# etapa1.net
KiCad netlist of a schematic drawn in Altium Designer
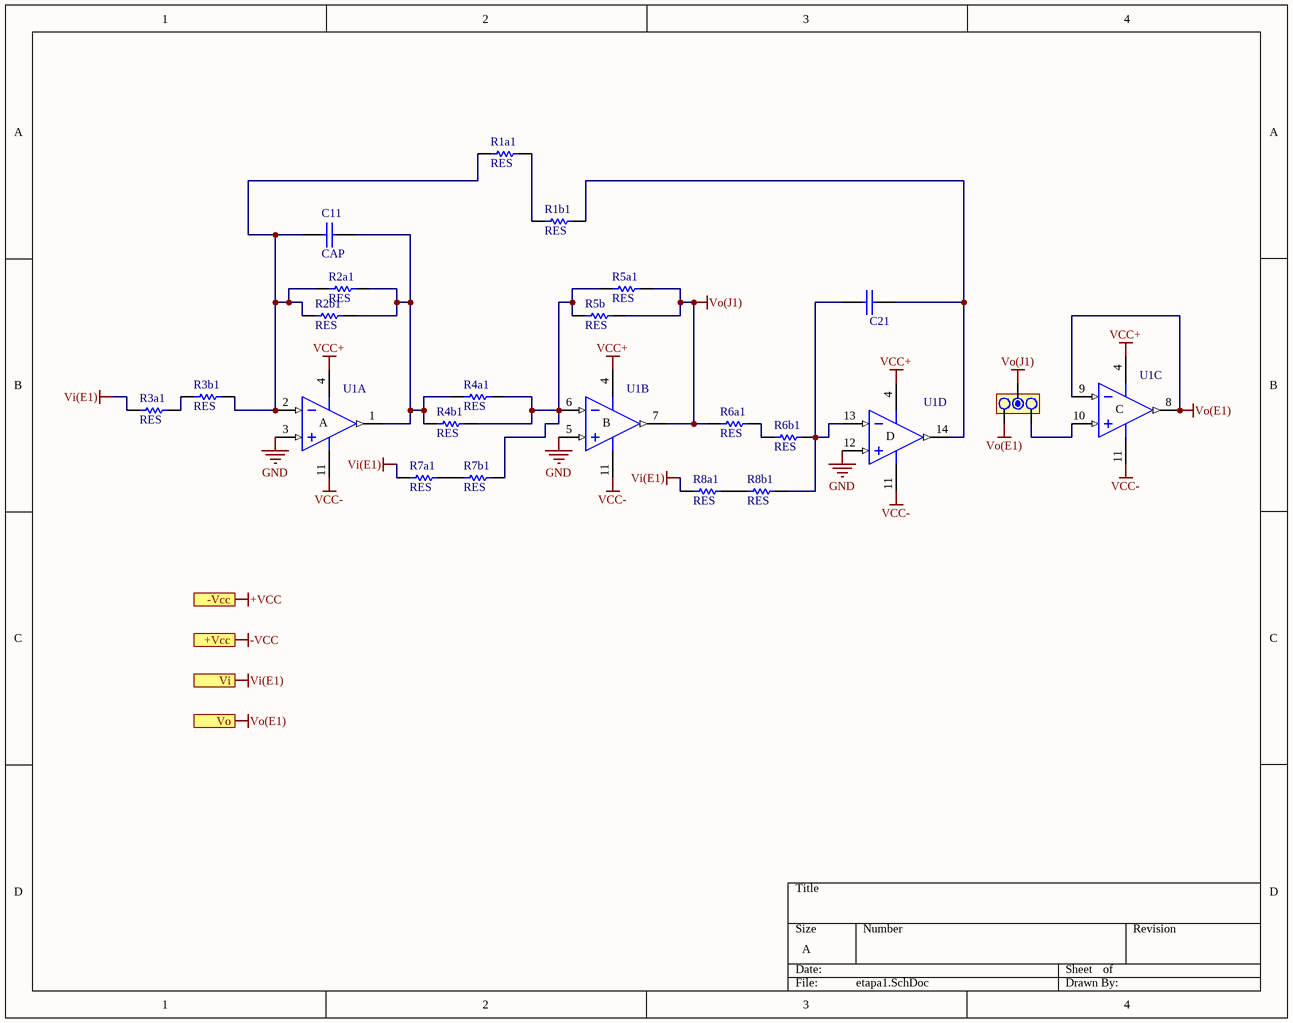
[diagram p0: etapa1.SchDoc]

(export (version "E")
  (design (tool "Eeschema 10.0.6"))
  (components
    (comp (ref "C11") (value "CAP") (footprint "CAP200") (libsource (lib "LIBEBAL") (part "CAP")))
    (comp (ref "C21") (value "CAP") (footprint "CAP200") (libsource (lib "LIBEBAL") (part "CAP")))
    (comp (ref "Jumper1") (value "JUMPER") (footprint "JUMPER3") (libsource (lib "LIBEBAL") (part "JUMPER3")))
    (comp (ref "R1a1") (value "RES") (footprint "0805") (libsource (lib "LIBEBAL") (part "RES")))
    (comp (ref "R1b1") (value "RES") (footprint "0805") (libsource (lib "LIBEBAL") (part "RES")))
    (comp (ref "R2a1") (value "RES") (footprint "0805") (libsource (lib "LIBEBAL") (part "RES")))
    (comp (ref "R2b1") (value "RES") (footprint "0805") (libsource (lib "LIBEBAL") (part "RES")))
    (comp (ref "R3a1") (value "RES") (footprint "0805") (libsource (lib "LIBEBAL") (part "RES")))
    (comp (ref "R3b1") (value "RES") (footprint "0805") (libsource (lib "LIBEBAL") (part "RES")))
    (comp (ref "R4a1") (value "RES") (footprint "0805") (libsource (lib "LIBEBAL") (part "RES")))
    (comp (ref "R4b1") (value "RES") (footprint "0805") (libsource (lib "LIBEBAL") (part "RES")))
    (comp (ref "R5a1") (value "RES") (footprint "0805") (libsource (lib "LIBEBAL") (part "RES")))
    (comp (ref "R5b") (value "RES") (footprint "0805") (libsource (lib "LIBEBAL") (part "RES")))
    (comp (ref "R6a1") (value "RES") (footprint "0805") (libsource (lib "LIBEBAL") (part "RES")))
    (comp (ref "R6b1") (value "RES") (footprint "0805") (libsource (lib "LIBEBAL") (part "RES")))
    (comp (ref "R7a1") (value "RES") (footprint "0805") (libsource (lib "LIBEBAL") (part "RES")))
    (comp (ref "R7b1") (value "RES") (footprint "0805") (libsource (lib "LIBEBAL") (part "RES")))
    (comp (ref "R8a1") (value "RES") (footprint "0805") (libsource (lib "LIBEBAL") (part "RES")))
    (comp (ref "R8b1") (value "RES") (footprint "0805") (libsource (lib "LIBEBAL") (part "RES")))
    (comp (ref "U1")
      (value "TL084N")
      (footprint "N014")
      (description "JFET-Input Operational Amplifier")
      (fields (field (name "PUBLISHER") "Altium Limited"))
      (libsource (lib "TI Operational Amplifier") (part "TL084N"))
    )
  )
  (nets
    (net (code "3") (name "GND") (class "Default")
      (node (ref "U1") (pin "12") (pinfunction "IN+_12") (pintype "input"))
      (node (ref "U1") (pin "3") (pinfunction "IN+_3") (pintype "input"))
      (node (ref "U1") (pin "5") (pinfunction "IN+_5") (pintype "input"))
    )
    (net (code "4") (name "Net-(R1a1-Pad2)") (class "Default")
      (node (ref "R1a1") (pin "2") (pinfunction "2_2") (pintype "passive"))
      (node (ref "R1b1") (pin "1") (pinfunction "1_1") (pintype "passive"))
    )
    (net (code "5") (name "Net-(R3a1-Pad2)") (class "Default")
      (node (ref "R3a1") (pin "2") (pinfunction "2_2") (pintype "passive"))
      (node (ref "R3b1") (pin "1") (pinfunction "1_1") (pintype "passive"))
    )
    (net (code "6") (name "Net-(R6a1-Pad2)") (class "Default")
      (node (ref "R6a1") (pin "2") (pinfunction "2_2") (pintype "passive"))
      (node (ref "R6b1") (pin "1") (pinfunction "1_1") (pintype "passive"))
    )
    (net (code "7") (name "Net-(R7a1-Pad2)") (class "Default")
      (node (ref "R7a1") (pin "2") (pinfunction "2_2") (pintype "passive"))
      (node (ref "R7b1") (pin "1") (pinfunction "1_1") (pintype "passive"))
    )
    (net (code "8") (name "Net-(R8a1-Pad2)") (class "Default")
      (node (ref "R8a1") (pin "2") (pinfunction "2_2") (pintype "passive"))
      (node (ref "R8b1") (pin "1") (pinfunction "1_1") (pintype "passive"))
    )
    (net (code "9") (name "Net-(U1A-IN-)") (class "Default")
      (node (ref "C11") (pin "1") (pinfunction "1_1") (pintype "passive"))
      (node (ref "R1a1") (pin "1") (pinfunction "1_1") (pintype "passive"))
      (node (ref "R2a1") (pin "1") (pinfunction "1_1") (pintype "passive"))
      (node (ref "R2b1") (pin "1") (pinfunction "1_1") (pintype "passive"))
      (node (ref "R3b1") (pin "2") (pinfunction "2_2") (pintype "passive"))
      (node (ref "U1") (pin "2") (pinfunction "IN-_2") (pintype "input"))
    )
    (net (code "10") (name "Net-(U1A-OUT)") (class "Default")
      (node (ref "C11") (pin "2") (pinfunction "2_2") (pintype "passive"))
      (node (ref "R2a1") (pin "2") (pinfunction "2_2") (pintype "passive"))
      (node (ref "R2b1") (pin "2") (pinfunction "2_2") (pintype "passive"))
      (node (ref "R4a1") (pin "1") (pinfunction "1_1") (pintype "passive"))
      (node (ref "R4b1") (pin "1") (pinfunction "1_1") (pintype "passive"))
      (node (ref "U1") (pin "1") (pinfunction "OUT_1") (pintype "output"))
    )
    (net (code "11") (name "Net-(U1B-IN-)") (class "Default")
      (node (ref "R4a1") (pin "2") (pinfunction "2_2") (pintype "passive"))
      (node (ref "R4b1") (pin "2") (pinfunction "2_2") (pintype "passive"))
      (node (ref "R5a1") (pin "1") (pinfunction "1_1") (pintype "passive"))
      (node (ref "R5b") (pin "1") (pinfunction "1_1") (pintype "passive"))
      (node (ref "R7b1") (pin "2") (pinfunction "2_2") (pintype "passive"))
      (node (ref "U1") (pin "6") (pinfunction "IN-_6") (pintype "input"))
    )
    (net (code "12") (name "Net-(U1C-IN+)") (class "Default")
      (node (ref "Jumper1") (pin "1") (pinfunction "1_1") (pintype "passive"))
      (node (ref "U1") (pin "10") (pinfunction "IN+_10") (pintype "input"))
    )
    (net (code "13") (name "Net-(U1D-IN-)") (class "Default")
      (node (ref "C21") (pin "1") (pinfunction "1_1") (pintype "passive"))
      (node (ref "R6b1") (pin "2") (pinfunction "2_2") (pintype "passive"))
      (node (ref "R8b1") (pin "2") (pinfunction "2_2") (pintype "passive"))
      (node (ref "U1") (pin "13") (pinfunction "IN-_13") (pintype "input"))
    )
    (net (code "14") (name "Net-(U1D-OUT)") (class "Default")
      (node (ref "C21") (pin "2") (pinfunction "2_2") (pintype "passive"))
      (node (ref "R1b1") (pin "2") (pinfunction "2_2") (pintype "passive"))
      (node (ref "U1") (pin "14") (pinfunction "OUT_14") (pintype "output"))
    )
    (net (code "15") (name "VCC+") (class "Default")
      (node (ref "U1") (pin "4") (pinfunction "V+_4") (pintype "power_in"))
    )
    (net (code "16") (name "VCC-") (class "Default")
      (node (ref "U1") (pin "11") (pinfunction "V-_11") (pintype "power_in"))
    )
    (net (code "17") (name "Vi(E1)") (class "Default")
      (node (ref "R3a1") (pin "1") (pinfunction "1_1") (pintype "passive"))
      (node (ref "R7a1") (pin "1") (pinfunction "1_1") (pintype "passive"))
      (node (ref "R8a1") (pin "1") (pinfunction "1_1") (pintype "passive"))
    )
    (net (code "18") (name "Vo(E1)") (class "Default")
      (node (ref "Jumper1") (pin "3") (pinfunction "3_3") (pintype "passive"))
      (node (ref "U1") (pin "8") (pinfunction "OUT_8") (pintype "output"))
      (node (ref "U1") (pin "9") (pinfunction "IN-_9") (pintype "input"))
    )
    (net (code "19") (name "Vo(J1)") (class "Default")
      (node (ref "Jumper1") (pin "2") (pinfunction "2_2") (pintype "passive"))
      (node (ref "R5a1") (pin "2") (pinfunction "2_2") (pintype "passive"))
      (node (ref "R5b") (pin "2") (pinfunction "2_2") (pintype "passive"))
      (node (ref "R6a1") (pin "1") (pinfunction "1_1") (pintype "passive"))
      (node (ref "U1") (pin "7") (pinfunction "OUT_7") (pintype "output"))
    )
  )
)
